# LED_Driver_QBHP686.net
KiCad netlist of a schematic drawn in Altium Designer
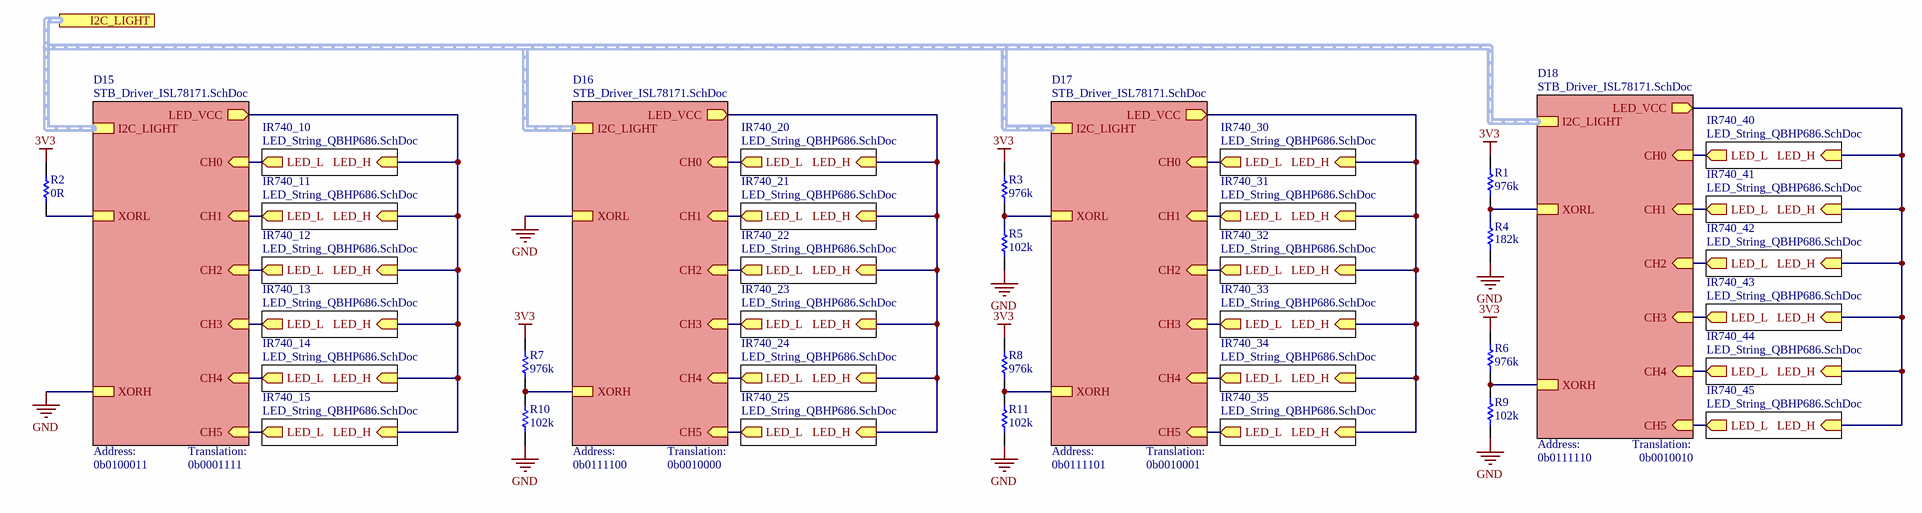
[diagram p0: LED_Driver_QBHP686.SchDoc]

(export (version "E")
  (design (tool "Eeschema 10.0.6"))
  (components
    (comp (ref "R1")
      (value "976k")
      (footprint "RESC1005X40X25LL05T05")
      (fields
        (field (name "MANUFACTURER") "Panasonic")
        (field (name "PART NUMBER") "ERJ-2RKF9763X")
        (field (name "TOLERANCE") "1%")
      )
      (libsource (lib "Altium Content Vault") (part "RES"))
    )
    (comp (ref "R2")
      (value "0R")
      (footprint "RESC1005X40X25LL05T10")
      (fields (field (name "MANUFACTURER") "Yageo / Phycomp") (field (name "PART NUMBER") "RC0402JR-070RL"))
      (libsource (lib "Altium Content Vault") (part "RES"))
    )
    (comp (ref "R3")
      (value "976k")
      (footprint "RESC1005X40X25LL05T05")
      (fields
        (field (name "MANUFACTURER") "Panasonic")
        (field (name "PART NUMBER") "ERJ-2RKF9763X")
        (field (name "TOLERANCE") "1%")
      )
      (libsource (lib "Altium Content Vault") (part "RES"))
    )
    (comp (ref "R4")
      (value "182k")
      (footprint "RESC1005X40X25LL05T05")
      (fields
        (field (name "MANUFACTURER") "Vishay Dale")
        (field (name "PART NUMBER") "CRCW0402182KFKED")
        (field (name "TOLERANCE") "1%")
      )
      (libsource (lib "Altium Content Vault") (part "RES"))
    )
    (comp (ref "R5")
      (value "102k")
      (footprint "RESC1005X40X25LL05T05")
      (fields
        (field (name "MANUFACTURER") "Panasonic")
        (field (name "PART NUMBER") "ERJ-2RKF1023X")
        (field (name "TOLERANCE") "1%")
      )
      (libsource (lib "Altium Content Vault") (part "RES"))
    )
    (comp (ref "R6")
      (value "976k")
      (footprint "RESC1005X40X25LL05T05")
      (fields
        (field (name "MANUFACTURER") "Panasonic")
        (field (name "PART NUMBER") "ERJ-2RKF9763X")
        (field (name "TOLERANCE") "1%")
      )
      (libsource (lib "Altium Content Vault") (part "RES"))
    )
    (comp (ref "R7")
      (value "976k")
      (footprint "RESC1005X40X25LL05T05")
      (fields
        (field (name "MANUFACTURER") "Panasonic")
        (field (name "PART NUMBER") "ERJ-2RKF9763X")
        (field (name "TOLERANCE") "1%")
      )
      (libsource (lib "Altium Content Vault") (part "RES"))
    )
    (comp (ref "R8")
      (value "976k")
      (footprint "RESC1005X40X25LL05T05")
      (fields
        (field (name "MANUFACTURER") "Panasonic")
        (field (name "PART NUMBER") "ERJ-2RKF9763X")
        (field (name "TOLERANCE") "1%")
      )
      (libsource (lib "Altium Content Vault") (part "RES"))
    )
    (comp (ref "R9")
      (value "102k")
      (footprint "RESC1005X40X25LL05T05")
      (fields
        (field (name "MANUFACTURER") "Panasonic")
        (field (name "PART NUMBER") "ERJ-2RKF1023X")
        (field (name "TOLERANCE") "1%")
      )
      (libsource (lib "Altium Content Vault") (part "RES"))
    )
    (comp (ref "R10")
      (value "102k")
      (footprint "RESC1005X40X25LL05T05")
      (fields
        (field (name "MANUFACTURER") "Panasonic")
        (field (name "PART NUMBER") "ERJ-2RKF1023X")
        (field (name "TOLERANCE") "1%")
      )
      (libsource (lib "Altium Content Vault") (part "RES"))
    )
    (comp (ref "R11")
      (value "102k")
      (footprint "RESC1005X40X25LL05T05")
      (fields
        (field (name "MANUFACTURER") "Panasonic")
        (field (name "PART NUMBER") "ERJ-2RKF1023X")
        (field (name "TOLERANCE") "1%")
      )
      (libsource (lib "Altium Content Vault") (part "RES"))
    )
  )
  (nets
    (net (code "31") (name "/XORH") (class "Default")
      (node (ref "R6") (pin "1") (pinfunction "1_1") (pintype "passive"))
      (node (ref "R9") (pin "2") (pinfunction "2_2") (pintype "passive"))
    )
    (net (code "32") (name "/XORH_1") (class "Default")
      (node (ref "R11") (pin "2") (pinfunction "2_2") (pintype "passive"))
      (node (ref "R8") (pin "1") (pinfunction "1_1") (pintype "passive"))
    )
    (net (code "33") (name "/XORH_2") (class "Default")
      (node (ref "R10") (pin "2") (pinfunction "2_2") (pintype "passive"))
      (node (ref "R7") (pin "1") (pinfunction "1_1") (pintype "passive"))
    )
    (net (code "34") (name "/XORL") (class "Default")
      (node (ref "R1") (pin "1") (pinfunction "1_1") (pintype "passive"))
      (node (ref "R4") (pin "2") (pinfunction "2_2") (pintype "passive"))
    )
    (net (code "35") (name "/XORL_1") (class "Default")
      (node (ref "R2") (pin "1") (pinfunction "1_1") (pintype "passive"))
    )
    (net (code "36") (name "/XORL_2") (class "Default")
      (node (ref "R3") (pin "1") (pinfunction "1_1") (pintype "passive"))
      (node (ref "R5") (pin "2") (pinfunction "2_2") (pintype "passive"))
    )
    (net (code "37") (name "3V3") (class "Default")
      (node (ref "R1") (pin "2") (pinfunction "2_2") (pintype "passive"))
      (node (ref "R2") (pin "2") (pinfunction "2_2") (pintype "passive"))
      (node (ref "R3") (pin "2") (pinfunction "2_2") (pintype "passive"))
      (node (ref "R6") (pin "2") (pinfunction "2_2") (pintype "passive"))
      (node (ref "R7") (pin "2") (pinfunction "2_2") (pintype "passive"))
      (node (ref "R8") (pin "2") (pinfunction "2_2") (pintype "passive"))
    )
    (net (code "38") (name "GND") (class "Default")
      (node (ref "R10") (pin "1") (pinfunction "1_1") (pintype "passive"))
      (node (ref "R11") (pin "1") (pinfunction "1_1") (pintype "passive"))
      (node (ref "R4") (pin "1") (pinfunction "1_1") (pintype "passive"))
      (node (ref "R5") (pin "1") (pinfunction "1_1") (pintype "passive"))
      (node (ref "R9") (pin "1") (pinfunction "1_1") (pintype "passive"))
    )
  )
)
